# schema.net
KiCad netlist of a schematic drawn in EAGLE
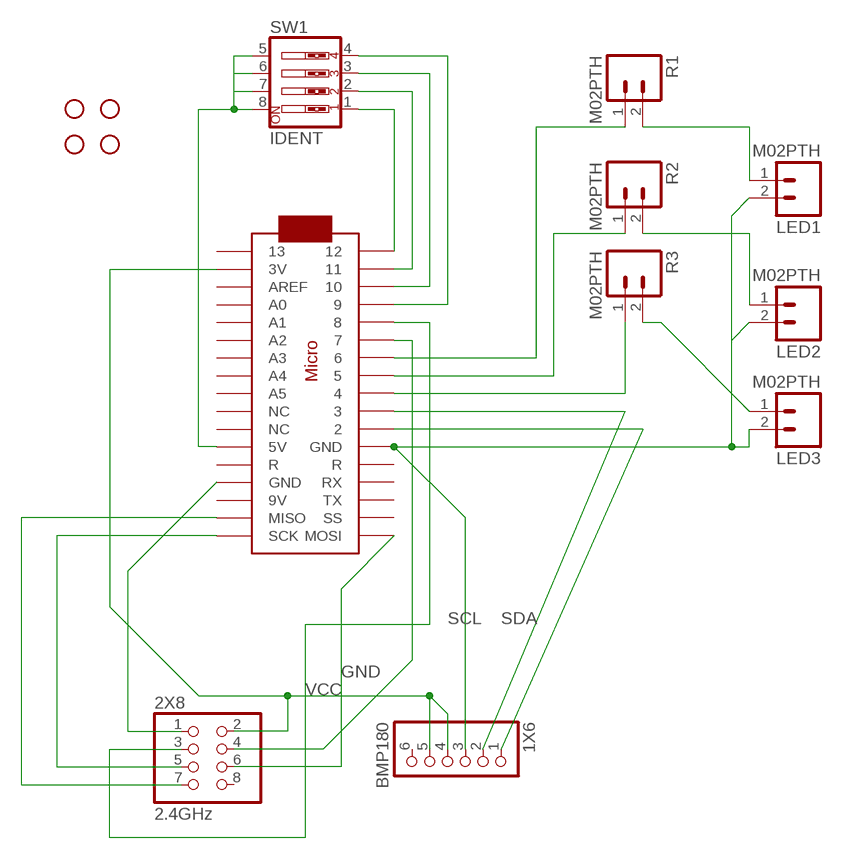
[diagram p0: schematic, sheet 1]

(export (version "E")
  (design (tool "Eeschema 10.0.6"))
  (components
    (comp (ref "1X6")
      (value "BMP180")
      (footprint "eagle-import:1X06")
      (libsource (lib "eagle-import") (part "PINHD-1X6"))
    )
    (comp (ref "2X8")
      (value "2.4GHz")
      (footprint "eagle-import:2X04")
      (libsource (lib "eagle-import") (part "PINHD-2X4"))
    )
    (comp (ref "LED1")
      (value "M02PTH")
      (footprint "eagle-import:1X02")
      (libsource (lib "eagle-import") (part "M02PTH"))
    )
    (comp (ref "LED2")
      (value "M02PTH")
      (footprint "eagle-import:1X02")
      (libsource (lib "eagle-import") (part "M02PTH"))
    )
    (comp (ref "LED3")
      (value "M02PTH")
      (footprint "eagle-import:1X02")
      (libsource (lib "eagle-import") (part "M02PTH"))
    )
    (comp (ref "R1")
      (value "M02PTH")
      (footprint "eagle-import:1X02")
      (libsource (lib "eagle-import") (part "M02PTH"))
    )
    (comp (ref "R2")
      (value "M02PTH")
      (footprint "eagle-import:1X02")
      (libsource (lib "eagle-import") (part "M02PTH"))
    )
    (comp (ref "R3")
      (value "M02PTH")
      (footprint "eagle-import:1X02")
      (libsource (lib "eagle-import") (part "M02PTH"))
    )
    (comp (ref "STANDOFF1")
      (value "STAND-OFF")
      (footprint "eagle-import:STAND-OFF")
      (libsource (lib "eagle-import") (part "STAND-OFF"))
    )
    (comp (ref "STANDOFF2")
      (value "STAND-OFF")
      (footprint "eagle-import:STAND-OFF")
      (libsource (lib "eagle-import") (part "STAND-OFF"))
    )
    (comp (ref "STANDOFF3")
      (value "STAND-OFF")
      (footprint "eagle-import:STAND-OFF")
      (libsource (lib "eagle-import") (part "STAND-OFF"))
    )
    (comp (ref "STANDOFF4")
      (value "STAND-OFF")
      (footprint "eagle-import:STAND-OFF")
      (libsource (lib "eagle-import") (part "STAND-OFF"))
    )
    (comp (ref "SW1")
      (value "IDENT")
      (footprint "eagle-import:EDG-04")
      (libsource (lib "eagle-import") (part "SW_DIP-4"))
    )
    (comp (ref "U$1")
      (value "ARDUINOMICRO")
      (footprint "eagle-import:ARDUINOMICRO")
      (libsource (lib "eagle-import") (part "ARDUINOMICRO"))
    )
  )
  (nets
    (net (code "1") (name "/GND") (class "Default")
      (node (ref "1X6") (pin "3") (pinfunction "3_3") (pintype "passive"))
      (node (ref "2X8") (pin "1") (pinfunction "1_1") (pintype "passive"))
      (node (ref "LED1") (pin "2") (pinfunction "2_2") (pintype "passive"))
      (node (ref "LED2") (pin "2") (pinfunction "2_2") (pintype "passive"))
      (node (ref "LED3") (pin "2") (pinfunction "2_2") (pintype "passive"))
      (node (ref "U$1") (pin "P$12") (pinfunction "GND_P$12") (pintype "bidirectional"))
      (node (ref "U$1") (pin "P$21") (pinfunction "GND_P$21") (pintype "bidirectional"))
    )
    (net (code "2") (name "/SCL") (class "Default")
      (node (ref "1X6") (pin "2") (pinfunction "2_2") (pintype "passive"))
      (node (ref "U$1") (pin "P$10") (pinfunction "3_P$10") (pintype "bidirectional"))
    )
    (net (code "3") (name "/SDA") (class "Default")
      (node (ref "1X6") (pin "1") (pinfunction "1_1") (pintype "passive"))
      (node (ref "U$1") (pin "P$11") (pinfunction "2_P$11") (pintype "bidirectional"))
    )
    (net (code "4") (name "/VCC") (class "Default")
      (node (ref "1X6") (pin "4") (pinfunction "4_4") (pintype "passive"))
      (node (ref "1X6") (pin "5") (pinfunction "5_5") (pintype "passive"))
      (node (ref "2X8") (pin "2") (pinfunction "2_2") (pintype "passive"))
      (node (ref "U$1") (pin "P$33") (pinfunction "3V_P$33") (pintype "bidirectional"))
    )
    (net (code "5") (name "Net-(LED1-Pad1)") (class "Default")
      (node (ref "LED1") (pin "1") (pinfunction "1_1") (pintype "passive"))
      (node (ref "R1") (pin "2") (pinfunction "2_2") (pintype "passive"))
    )
    (net (code "6") (name "Net-(LED2-Pad1)") (class "Default")
      (node (ref "LED2") (pin "1") (pinfunction "1_1") (pintype "passive"))
      (node (ref "R2") (pin "2") (pinfunction "2_2") (pintype "passive"))
    )
    (net (code "7") (name "Net-(LED3-Pad1)") (class "Default")
      (node (ref "LED3") (pin "1") (pinfunction "1_1") (pintype "passive"))
      (node (ref "R3") (pin "2") (pinfunction "2_2") (pintype "passive"))
    )
    (net (code "8") (name "Net-(U$1-4)") (class "Default")
      (node (ref "R3") (pin "1") (pinfunction "1_1") (pintype "passive"))
      (node (ref "U$1") (pin "P$9") (pinfunction "4_P$9") (pintype "bidirectional"))
    )
    (net (code "9") (name "Net-(U$1-5)") (class "Default")
      (node (ref "R2") (pin "1") (pinfunction "1_1") (pintype "passive"))
      (node (ref "U$1") (pin "P$8") (pinfunction "5_P$8") (pintype "bidirectional"))
    )
    (net (code "10") (name "Net-(U$1-5V)") (class "Default")
      (node (ref "SW1") (pin "5") (pinfunction "5_5") (pintype "passive"))
      (node (ref "SW1") (pin "6") (pinfunction "6_6") (pintype "passive"))
      (node (ref "SW1") (pin "7") (pinfunction "7_7") (pintype "passive"))
      (node (ref "SW1") (pin "8") (pinfunction "8_8") (pintype "passive"))
      (node (ref "U$1") (pin "P$23") (pinfunction "5V_P$23") (pintype "bidirectional"))
    )
    (net (code "11") (name "Net-(U$1-6)") (class "Default")
      (node (ref "R1") (pin "1") (pinfunction "1_1") (pintype "passive"))
      (node (ref "U$1") (pin "P$7") (pinfunction "6_P$7") (pintype "bidirectional"))
    )
    (net (code "12") (name "Net-(U$1-7)") (class "Default")
      (node (ref "2X8") (pin "4") (pinfunction "4_4") (pintype "passive"))
      (node (ref "U$1") (pin "P$6") (pinfunction "7_P$6") (pintype "bidirectional"))
    )
    (net (code "13") (name "Net-(U$1-8)") (class "Default")
      (node (ref "2X8") (pin "3") (pinfunction "3_3") (pintype "passive"))
      (node (ref "U$1") (pin "P$5") (pinfunction "8_P$5") (pintype "bidirectional"))
    )
    (net (code "14") (name "Net-(U$1-9)") (class "Default")
      (node (ref "SW1") (pin "4") (pinfunction "4_4") (pintype "passive"))
      (node (ref "U$1") (pin "P$4") (pinfunction "9_P$4") (pintype "bidirectional"))
    )
    (net (code "15") (name "Net-(U$1-10)") (class "Default")
      (node (ref "SW1") (pin "3") (pinfunction "3_3") (pintype "passive"))
      (node (ref "U$1") (pin "P$3") (pinfunction "10_P$3") (pintype "bidirectional"))
    )
    (net (code "16") (name "Net-(U$1-11)") (class "Default")
      (node (ref "SW1") (pin "2") (pinfunction "2_2") (pintype "passive"))
      (node (ref "U$1") (pin "P$2") (pinfunction "11_P$2") (pintype "bidirectional"))
    )
    (net (code "17") (name "Net-(U$1-12)") (class "Default")
      (node (ref "SW1") (pin "1") (pinfunction "1_1") (pintype "passive"))
      (node (ref "U$1") (pin "P$1") (pinfunction "12_P$1") (pintype "bidirectional"))
    )
    (net (code "18") (name "Net-(U$1-MISO)") (class "Default")
      (node (ref "2X8") (pin "7") (pinfunction "7_7") (pintype "passive"))
      (node (ref "U$1") (pin "P$19") (pinfunction "MISO_P$19") (pintype "bidirectional"))
    )
    (net (code "19") (name "Net-(U$1-MOSI)") (class "Default")
      (node (ref "2X8") (pin "6") (pinfunction "6_6") (pintype "passive"))
      (node (ref "U$1") (pin "P$17") (pinfunction "MOSI_P$17") (pintype "bidirectional"))
    )
    (net (code "20") (name "Net-(U$1-SCK)") (class "Default")
      (node (ref "2X8") (pin "5") (pinfunction "5_5") (pintype "passive"))
      (node (ref "U$1") (pin "P$18") (pinfunction "SCK_P$18") (pintype "bidirectional"))
    )
    (net (code "21") (name "unconnected-(1X6-Pad6)") (class "Default")
      (node (ref "1X6") (pin "6") (pinfunction "6_6") (pintype "passive"))
    )
    (net (code "22") (name "unconnected-(2X8-Pad8)") (class "Default")
      (node (ref "2X8") (pin "8") (pinfunction "8_8") (pintype "passive"))
    )
    (net (code "23") (name "unconnected-(U$1-9V-PadP$20)") (class "Default")
      (node (ref "U$1") (pin "P$20") (pinfunction "9V_P$20") (pintype "bidirectional"))
    )
    (net (code "24") (name "unconnected-(U$1-13-PadP$34)") (class "Default")
      (node (ref "U$1") (pin "P$34") (pinfunction "13_P$34") (pintype "bidirectional"))
    )
    (net (code "25") (name "unconnected-(U$1-A0-PadP$31)") (class "Default")
      (node (ref "U$1") (pin "P$31") (pinfunction "A0_P$31") (pintype "bidirectional"))
    )
    (net (code "26") (name "unconnected-(U$1-A1-PadP$30)") (class "Default")
      (node (ref "U$1") (pin "P$30") (pinfunction "A1_P$30") (pintype "bidirectional"))
    )
    (net (code "27") (name "unconnected-(U$1-A2-PadP$29)") (class "Default")
      (node (ref "U$1") (pin "P$29") (pinfunction "A2_P$29") (pintype "bidirectional"))
    )
    (net (code "28") (name "unconnected-(U$1-A3-PadP$28)") (class "Default")
      (node (ref "U$1") (pin "P$28") (pinfunction "A3_P$28") (pintype "bidirectional"))
    )
    (net (code "29") (name "unconnected-(U$1-A4-PadP$27)") (class "Default")
      (node (ref "U$1") (pin "P$27") (pinfunction "A4_P$27") (pintype "bidirectional"))
    )
    (net (code "30") (name "unconnected-(U$1-A5-PadP$26)") (class "Default")
      (node (ref "U$1") (pin "P$26") (pinfunction "A5_P$26") (pintype "bidirectional"))
    )
    (net (code "31") (name "unconnected-(U$1-AREF-PadP$32)") (class "Default")
      (node (ref "U$1") (pin "P$32") (pinfunction "AREF_P$32") (pintype "bidirectional"))
    )
    (net (code "32") (name "unconnected-(U$1-NC-PadP$24)") (class "Default")
      (node (ref "U$1") (pin "P$24") (pinfunction "NC_P$24") (pintype "bidirectional"))
    )
    (net (code "33") (name "unconnected-(U$1-NC-PadP$25)") (class "Default")
      (node (ref "U$1") (pin "P$25") (pinfunction "NC_P$25") (pintype "bidirectional"))
    )
    (net (code "34") (name "unconnected-(U$1-R-PadP$13)") (class "Default")
      (node (ref "U$1") (pin "P$13") (pinfunction "R_P$13") (pintype "bidirectional"))
    )
    (net (code "35") (name "unconnected-(U$1-R-PadP$22)") (class "Default")
      (node (ref "U$1") (pin "P$22") (pinfunction "R_P$22") (pintype "bidirectional"))
    )
    (net (code "36") (name "unconnected-(U$1-RX-PadP$14)") (class "Default")
      (node (ref "U$1") (pin "P$14") (pinfunction "RX_P$14") (pintype "bidirectional"))
    )
    (net (code "37") (name "unconnected-(U$1-SS-PadP$16)") (class "Default")
      (node (ref "U$1") (pin "P$16") (pinfunction "SS_P$16") (pintype "bidirectional"))
    )
    (net (code "38") (name "unconnected-(U$1-TX-PadP$15)") (class "Default")
      (node (ref "U$1") (pin "P$15") (pinfunction "TX_P$15") (pintype "bidirectional"))
    )
  )
)
